# LoRa_DEMO.net
KiCad netlist of a schematic drawn in Altium Designer
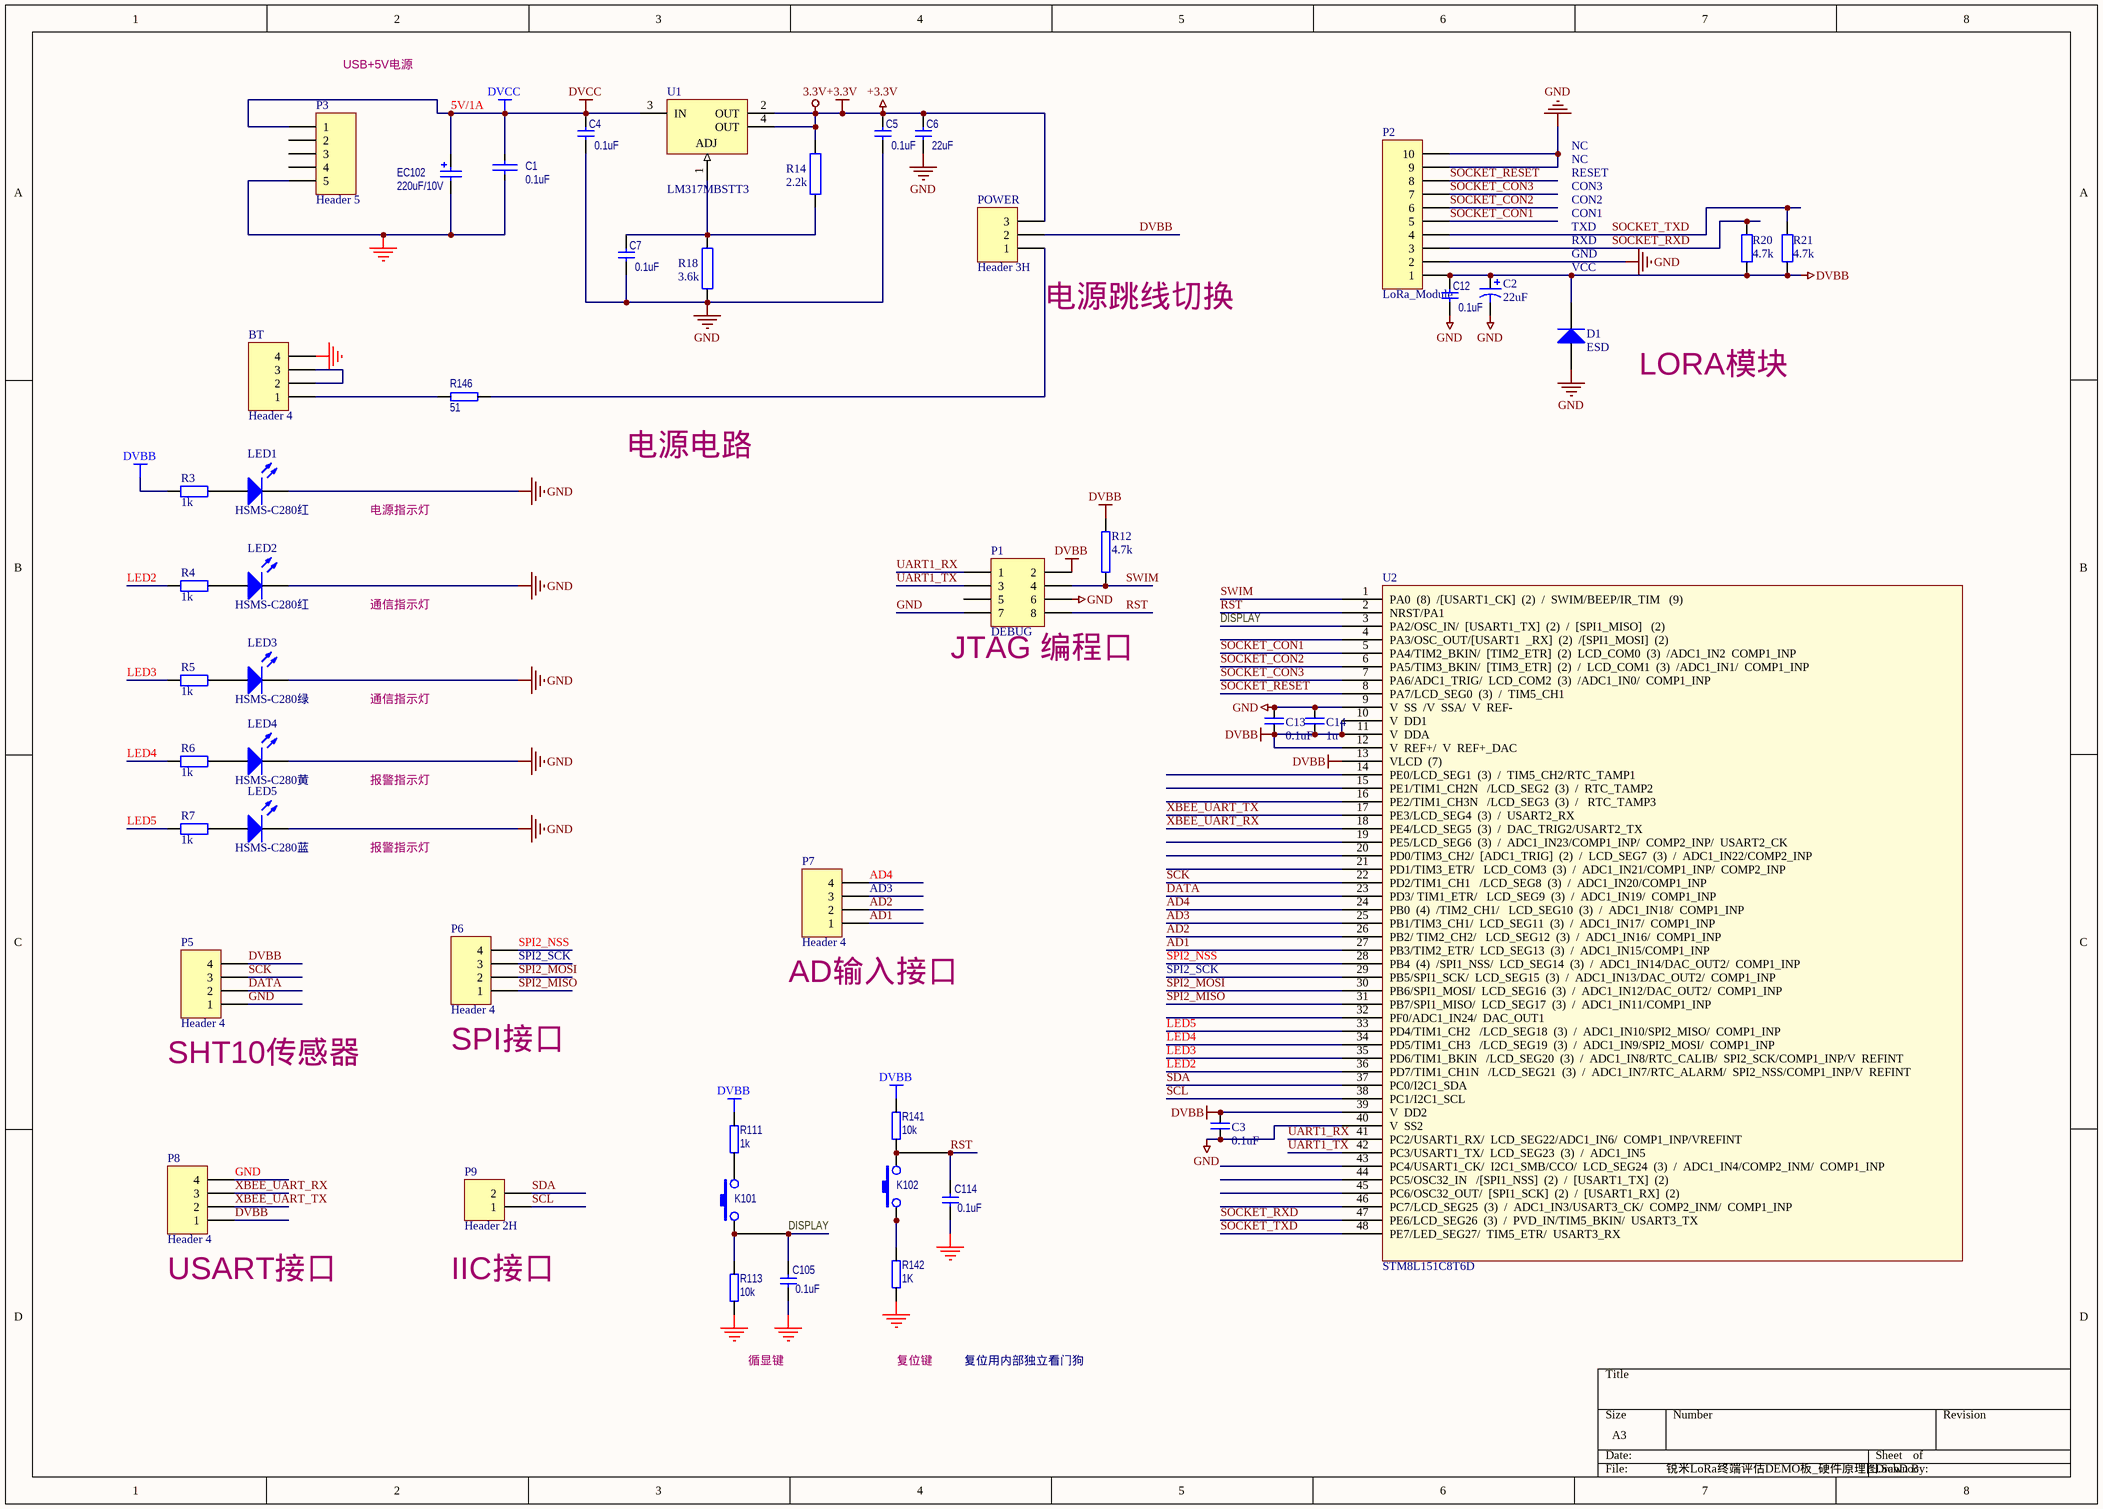
[diagram p0: 锐米LoRa终端评估DEMO板_硬件原理图.SchDoc]

(export (version "E")
  (design (tool "Eeschema 10.0.6"))
  (components
    (comp (ref "BT")
      (value "Header 4")
      (footprint "BT-1")
      (description "Header, 4-Pin")
      (fields (field (name "PUBLISHER") "Altium Limited"))
      (libsource (lib "Miscellaneous Connectors") (part "Header 4"))
    )
    (comp (ref "C1")
      (value "0.1uF")
      (footprint "0603C")
      (description "Capacitor")
      (libsource (lib "*") (part "CAP"))
    )
    (comp (ref "C2")
      (value "22uF")
      (footprint "3225[1210]")
      (description "Polarized Capacitor (Radial)")
      (fields (field (name "Comment") "Cap Pol1") (field (name "PUBLISHER") "Altium Limited"))
      (libsource (lib "Miscellaneous Devices") (part "Cap Pol1"))
    )
    (comp (ref "C3")
      (value "0.1uF")
      (footprint "0603C")
      (description "电容__贴片")
      (libsource (lib "*") (part "0603_50V_15pF±5% NPO"))
    )
    (comp (ref "C4") (value "0.1uF") (footprint "0603c") (libsource (lib "*") (part "ProE.tmp_22p_13")))
    (comp (ref "C5") (value "0.1uF") (footprint "0603C") (libsource (lib "*") (part "ProE.tmp_22p_13")))
    (comp (ref "C6") (value "22uF") (footprint "3225[1210]") (libsource (lib "*") (part "ProE.tmp_22p_13")))
    (comp (ref "C7") (value "0.1uF") (footprint "0603C") (libsource (lib "*") (part "ProE.tmp_22p_13")))
    (comp (ref "C12") (value "0.1uF") (footprint "0603C") (libsource (lib "*") (part "ProE.tmp_22p_13")))
    (comp (ref "C13")
      (value "0.1uF")
      (footprint "0603C")
      (description "电容__贴片")
      (libsource (lib "*") (part "0603_50V_15pF±5% NPO"))
    )
    (comp (ref "C14")
      (value "1u")
      (footprint "0603C")
      (description "电容__贴片")
      (libsource (lib "*") (part "0603_50V_15pF±5% NPO"))
    )
    (comp (ref "C105") (value "0.1uF") (footprint "0603C") (libsource (lib "*") (part "ProE.tmp_22p_13")))
    (comp (ref "C114") (value "0.1uF") (footprint "0603C") (libsource (lib "*") (part "ProE.tmp_22p_13")))
    (comp (ref "D1")
      (value "ESD")
      (footprint "SOD123/X.85")
      (description "Default Diode")
      (fields (field (name "PUBLISHER") "Altium Limited"))
      (libsource (lib "Miscellaneous Devices") (part "Diode"))
    )
    (comp (ref "EC102")
      (value "220uF/10V")
      (footprint "3225[1210]")
      (description "Polarized Capacitor (Radial)")
      (fields (field (name "PUBLISHER") "*"))
      (libsource (lib "*") (part "Cap Pol1"))
    )
    (comp (ref "K101") (value "~") (footprint "KEYSMT") (libsource (lib "*") (part "SW-PB")))
    (comp (ref "K102") (value "~") (footprint "KEYSMT") (libsource (lib "*") (part "SW-PB")))
    (comp (ref "LED1")
      (value "HSMS-C280红")
      (footprint "LED-SOP")
      (description "Miniature Chip LED, Red")
      (fields (field (name "PUBLISHER") "Altium Limited"))
      (libsource (lib "Agilent Optoelectronic LED") (part "HSMS-C280"))
    )
    (comp (ref "LED2")
      (value "HSMS-C280红")
      (footprint "LED-SOP")
      (description "Miniature Chip LED, Red")
      (fields (field (name "PUBLISHER") "Altium Limited"))
      (libsource (lib "Agilent Optoelectronic LED") (part "HSMS-C280"))
    )
    (comp (ref "LED3")
      (value "HSMS-C280绿")
      (footprint "LED-SOP")
      (description "Miniature Chip LED, Red")
      (fields (field (name "PUBLISHER") "Altium Limited"))
      (libsource (lib "Agilent Optoelectronic LED") (part "HSMS-C280"))
    )
    (comp (ref "LED4")
      (value "HSMS-C280黄")
      (footprint "LED-SOP")
      (description "Miniature Chip LED, Red")
      (fields (field (name "PUBLISHER") "Altium Limited"))
      (libsource (lib "Agilent Optoelectronic LED") (part "HSMS-C280"))
    )
    (comp (ref "LED5")
      (value "HSMS-C280蓝")
      (footprint "LED-SOP")
      (description "Miniature Chip LED, Red")
      (fields (field (name "PUBLISHER") "Altium Limited"))
      (libsource (lib "Agilent Optoelectronic LED") (part "HSMS-C280"))
    )
    (comp (ref "P1")
      (value "DEBUG")
      (footprint "HDR-2X7-F-1.27MM_8")
      (description "Header, 4-Pin, Dual row")
      (fields (field (name "PUBLISHER") "Altium Limited"))
      (libsource (lib "Miscellaneous Connectors") (part "Header 4X2"))
    )
    (comp (ref "P2")
      (value "LoRa_Module")
      (footprint "LIRDA")
      (description "Header, 10-Pin")
      (fields (field (name "PUBLISHER") "Altium Limited"))
      (libsource (lib "Miscellaneous Connectors") (part "Header 10"))
    )
    (comp (ref "P3")
      (value "Header 5")
      (footprint "USB-MINI")
      (description "Header, 5-Pin")
      (fields (field (name "PUBLISHER") "Altium Limited"))
      (libsource (lib "Miscellaneous Connectors") (part "Header 5"))
    )
    (comp (ref "P5")
      (value "Header 4")
      (footprint "SHT10")
      (description "Header, 4-Pin")
      (fields (field (name "PUBLISHER") "Altium Limited"))
      (libsource (lib "Miscellaneous Connectors") (part "Header 4"))
    )
    (comp (ref "P6")
      (value "Header 4")
      (footprint "HDR1X4")
      (description "Header, 4-Pin")
      (fields (field (name "PUBLISHER") "Altium Limited"))
      (libsource (lib "Miscellaneous Connectors") (part "Header 4"))
    )
    (comp (ref "P7")
      (value "Header 4")
      (footprint "HDR1X4")
      (description "Header, 4-Pin")
      (fields (field (name "PUBLISHER") "Altium Limited"))
      (libsource (lib "Miscellaneous Connectors") (part "Header 4"))
    )
    (comp (ref "P8")
      (value "Header 4")
      (footprint "HDR1X4")
      (description "Header, 4-Pin")
      (fields (field (name "PUBLISHER") "Altium Limited"))
      (libsource (lib "Miscellaneous Connectors") (part "Header 4"))
    )
    (comp (ref "P9")
      (value "Header 2H")
      (footprint "SIP2")
      (description "Header, 2-Pin, Right Angle")
      (fields (field (name "PUBLISHER") "Altium Limited"))
      (libsource (lib "Miscellaneous Connectors") (part "Header 2H"))
    )
    (comp (ref "POWER")
      (value "Header 3H")
      (footprint "SIP3")
      (description "Header, 3-Pin, Right Angle")
      (fields (field (name "PUBLISHER") "Altium Limited"))
      (libsource (lib "Miscellaneous Connectors") (part "Header 3H"))
    )
    (comp (ref "R3")
      (value "1k")
      (footprint "0603R")
      (description "Resistor SMD - IEC symbol version")
      (fields (field (name "Comment") "Resistor"))
      (libsource (lib "SX1276_e268v01a") (part "Resistor"))
    )
    (comp (ref "R4")
      (value "1k")
      (footprint "0603R")
      (description "Resistor SMD - IEC symbol version")
      (fields (field (name "Comment") "Resistor"))
      (libsource (lib "SX1276_e268v01a") (part "Resistor"))
    )
    (comp (ref "R5")
      (value "1k")
      (footprint "0603R")
      (description "Resistor SMD - IEC symbol version")
      (fields (field (name "Comment") "Resistor"))
      (libsource (lib "SX1276_e268v01a") (part "Resistor"))
    )
    (comp (ref "R6")
      (value "1k")
      (footprint "0603R")
      (description "Resistor SMD - IEC symbol version")
      (fields (field (name "Comment") "Resistor"))
      (libsource (lib "SX1276_e268v01a") (part "Resistor"))
    )
    (comp (ref "R7")
      (value "1k")
      (footprint "0603R")
      (description "Resistor SMD - IEC symbol version")
      (fields (field (name "Comment") "Resistor"))
      (libsource (lib "SX1276_e268v01a") (part "Resistor"))
    )
    (comp (ref "R12")
      (value "4.7k")
      (footprint "0603R")
      (description "¹qªý")
      (libsource (lib "*") (part "RES2"))
    )
    (comp (ref "R14")
      (value "2.2k")
      (footprint "0603R")
      (description "电阻_贴片")
      (libsource (lib "*") (part "0603_20kΩ±1%100ppm/℃"))
    )
    (comp (ref "R18")
      (value "3.6k")
      (footprint "0603R")
      (description "电阻_贴片")
      (libsource (lib "*") (part "0603_20kΩ±1%100ppm/℃"))
    )
    (comp (ref "R20")
      (value "4.7k")
      (footprint "0603R")
      (description "Resistor SMD - IEC symbol version")
      (fields (field (name "Comment") "Resistor"))
      (libsource (lib "") (part "Resistor_1"))
    )
    (comp (ref "R21")
      (value "4.7k")
      (footprint "0603R")
      (description "Resistor SMD - IEC symbol version")
      (fields (field (name "Comment") "Resistor"))
      (libsource (lib "") (part "Resistor_1"))
    )
    (comp (ref "R111") (value "1k") (footprint "0603R") (libsource (lib "*") (part "ProE.tmp_10k_66")))
    (comp (ref "R113") (value "10k") (footprint "0603R") (libsource (lib "*") (part "ProE.tmp_10k_66")))
    (comp (ref "R141") (value "10k") (footprint "0603R") (libsource (lib "*") (part "ProE.tmp_10k_66")))
    (comp (ref "R142") (value "1K") (footprint "0603R") (libsource (lib "*") (part "ProE.tmp_10k_66")))
    (comp (ref "R146") (value "51") (footprint "0603R") (libsource (lib "*") (part "ProE.tmp_10k_66")))
    (comp (ref "U1")
      (value "LM317MBSTT3")
      (footprint "318E-04")
      (description "Three-Terminal Adjustable Output Positive Voltage Regulator")
      (fields (field (name "PUBLISHER") "Altium Limited"))
      (libsource (lib "ON Semi Power Mgt Voltage Regulator") (part "LM317MBSTT3"))
    )
    (comp (ref "U2")
      (value "STM8L151C8T6D")
      (footprint "LQFP48_L")
      (libsource (lib "Schlib1") (part "Component_1"))
    )
  )
  (nets
    (net (code "1") (name "+3.3V") (class "Default")
      (node (ref "C5") (pin "1") (pintype "passive"))
      (node (ref "C6") (pin "1") (pintype "passive"))
      (node (ref "POWER") (pin "3") (pinfunction "3_3") (pintype "passive"))
      (node (ref "R14") (pin "1") (pintype "passive"))
      (node (ref "U1") (pin "2") (pinfunction "OUT_2") (pintype "power_in"))
      (node (ref "U1") (pin "4") (pinfunction "OUT_4") (pintype "power_in"))
    )
    (net (code "2") (name "/AD1") (class "Default")
      (node (ref "P7") (pin "1") (pinfunction "1_1") (pintype "passive"))
      (node (ref "U2") (pin "27") (pinfunction "PB3/TIM2_ETR/__LCD_SEG13__(3)__/__ADC1_IN15/COMP1_INP_27") (pintype "passive"))
    )
    (net (code "3") (name "/AD2") (class "Default")
      (node (ref "P7") (pin "2") (pinfunction "2_2") (pintype "passive"))
      (node (ref "U2") (pin "26") (pinfunction "PB2/_TIM2_CH2/___LCD_SEG12__(3)__/__ADC1_IN16/__COMP1_INP_26") (pintype "passive"))
    )
    (net (code "4") (name "/AD3") (class "Default")
      (node (ref "P7") (pin "3") (pinfunction "3_3") (pintype "passive"))
      (node (ref "U2") (pin "25") (pinfunction "PB1/TIM3_CH1/__LCD_SEG11__(3)__/__ADC1_IN17/__COMP1_INP_25") (pintype "passive"))
    )
    (net (code "5") (name "/AD4") (class "Default")
      (node (ref "P7") (pin "4") (pinfunction "4_4") (pintype "passive"))
      (node (ref "U2") (pin "24") (pinfunction "PB0__(4)__/TIM2_CH1/___LCD_SEG10__(3)__/__ADC1_IN18/__COMP1_INP_24") (pintype "passive"))
    )
    (net (code "6") (name "/DATA") (class "Default")
      (node (ref "P5") (pin "2") (pinfunction "2_2") (pintype "passive"))
      (node (ref "U2") (pin "23") (pinfunction "PD3/_TIM1_ETR/___LCD_SEG9__(3)__/__ADC1_IN19/__COMP1_INP_23") (pintype "passive"))
    )
    (net (code "7") (name "/DISPLAY") (class "Default")
      (node (ref "C105") (pin "1") (pintype "passive"))
      (node (ref "K101") (pin "2") (pinfunction "2_2") (pintype "passive"))
      (node (ref "R113") (pin "1") (pintype "passive"))
      (node (ref "U2") (pin "3") (pinfunction "PA2/OSC_IN/__[USART1_TX]__(2)__/__[SPI1_MISO]___(2)_3") (pintype "passive"))
    )
    (net (code "8") (name "/LED2") (class "Default")
      (node (ref "R4") (pin "1") (pinfunction "1_1") (pintype "passive"))
      (node (ref "U2") (pin "36") (pinfunction "PD7/TIM1_CH1N___/LCD_SEG21__(3)__/__ADC1_IN7/RTC_ALARM/__SPI2_NSS/COMP1_INP/V__REFINT_36") (pintype "passive"))
    )
    (net (code "9") (name "/LED3") (class "Default")
      (node (ref "R5") (pin "1") (pinfunction "1_1") (pintype "passive"))
      (node (ref "U2") (pin "35") (pinfunction "PD6/TIM1_BKIN___/LCD_SEG20__(3)__/__ADC1_IN8/RTC_CALIB/__SPI2_SCK/COMP1_INP/V__REFINT_35") (pintype "passive"))
    )
    (net (code "10") (name "/LED4") (class "Default")
      (node (ref "R6") (pin "1") (pinfunction "1_1") (pintype "passive"))
      (node (ref "U2") (pin "34") (pinfunction "PD5/TIM1_CH3___/LCD_SEG19__(3)__/__ADC1_IN9/SPI2_MOSI/__COMP1_INP_34") (pintype "passive"))
    )
    (net (code "11") (name "/LED5") (class "Default")
      (node (ref "R7") (pin "1") (pinfunction "1_1") (pintype "passive"))
      (node (ref "U2") (pin "33") (pinfunction "PD4/TIM1_CH2___/LCD_SEG18__(3)__/__ADC1_IN10/SPI2_MISO/__COMP1_INP_33") (pintype "passive"))
    )
    (net (code "12") (name "/RST") (class "Default")
      (node (ref "C114") (pin "1") (pintype "passive"))
      (node (ref "K102") (pin "1") (pinfunction "1_1") (pintype "passive"))
      (node (ref "P1") (pin "8") (pinfunction "8_8") (pintype "passive"))
      (node (ref "R141") (pin "2") (pintype "passive"))
      (node (ref "U2") (pin "2") (pinfunction "NRST/PA1_2") (pintype "passive"))
    )
    (net (code "13") (name "/SCK") (class "Default")
      (node (ref "P5") (pin "3") (pinfunction "3_3") (pintype "passive"))
      (node (ref "U2") (pin "22") (pinfunction "PD2/TIM1_CH1___/LCD_SEG8__(3)__/__ADC1_IN20/COMP1_INP_22") (pintype "passive"))
    )
    (net (code "14") (name "/SCL") (class "Default")
      (node (ref "P9") (pin "1") (pinfunction "1_1") (pintype "passive"))
      (node (ref "U2") (pin "38") (pinfunction "PC1/I2C1_SCL_38") (pintype "passive"))
    )
    (net (code "15") (name "/SDA") (class "Default")
      (node (ref "P9") (pin "2") (pinfunction "2_2") (pintype "passive"))
      (node (ref "U2") (pin "37") (pinfunction "PC0/I2C1_SDA_37") (pintype "passive"))
    )
    (net (code "16") (name "/SOCKET_CON1") (class "Default")
      (node (ref "P2") (pin "5") (pinfunction "5_5") (pintype "passive"))
      (node (ref "U2") (pin "5") (pinfunction "PA4/TIM2_BKIN/__[TIM2_ETR]__(2)__LCD_COM0__(3)__/ADC1_IN2__COMP1_INP_5") (pintype "passive"))
    )
    (net (code "17") (name "/SOCKET_CON2") (class "Default")
      (node (ref "P2") (pin "6") (pinfunction "6_6") (pintype "passive"))
      (node (ref "U2") (pin "6") (pinfunction "PA5/TIM3_BKIN/__[TIM3_ETR]__(2)__/__LCD_COM1__(3)__/ADC1_IN1/__COMP1_INP_6") (pintype "passive"))
    )
    (net (code "18") (name "/SOCKET_CON3") (class "Default")
      (node (ref "P2") (pin "7") (pinfunction "7_7") (pintype "passive"))
      (node (ref "U2") (pin "7") (pinfunction "PA6/ADC1_TRIG/__LCD_COM2__(3)__/ADC1_IN0/__COMP1_INP_7") (pintype "passive"))
    )
    (net (code "19") (name "/SOCKET_RESET") (class "Default")
      (node (ref "P2") (pin "8") (pinfunction "8_8") (pintype "passive"))
      (node (ref "U2") (pin "8") (pinfunction "PA7/LCD_SEG0__(3)__/__TIM5_CH1_8") (pintype "passive"))
    )
    (net (code "20") (name "/SOCKET_RXD") (class "Default")
      (node (ref "P2") (pin "3") (pinfunction "3_3") (pintype "passive"))
      (node (ref "R20") (pin "2") (pinfunction "2_2") (pintype "passive"))
      (node (ref "U2") (pin "47") (pinfunction "PE6/LCD_SEG26__(3)__/__PVD_IN/TIM5_BKIN/__USART3_TX_47") (pintype "passive"))
    )
    (net (code "21") (name "/SOCKET_TXD") (class "Default")
      (node (ref "P2") (pin "4") (pinfunction "4_4") (pintype "passive"))
      (node (ref "R21") (pin "2") (pinfunction "2_2") (pintype "passive"))
      (node (ref "U2") (pin "48") (pinfunction "PE7/LED_SEG27/__TIM5_ETR/__USART3_RX_48") (pintype "passive"))
    )
    (net (code "22") (name "/SPI2_MISO") (class "Default")
      (node (ref "P6") (pin "1") (pinfunction "1_1") (pintype "passive"))
      (node (ref "U2") (pin "31") (pinfunction "PB7/SPI1_MISO/__LCD_SEG17__(3)__/__ADC1_IN11/COMP1_INP_31") (pintype "passive"))
    )
    (net (code "23") (name "/SPI2_MOSI") (class "Default")
      (node (ref "P6") (pin "2") (pinfunction "2_2") (pintype "passive"))
      (node (ref "U2") (pin "30") (pinfunction "PB6/SPI1_MOSI/__LCD_SEG16__(3)__/__ADC1_IN12/DAC_OUT2/__COMP1_INP_30") (pintype "passive"))
    )
    (net (code "24") (name "/SPI2_NSS") (class "Default")
      (node (ref "P6") (pin "4") (pinfunction "4_4") (pintype "passive"))
      (node (ref "U2") (pin "28") (pinfunction "PB4__(4)__/SPI1_NSS/__LCD_SEG14__(3)__/__ADC1_IN14/DAC_OUT2/__COMP1_INP_28") (pintype "passive"))
    )
    (net (code "25") (name "/SPI2_SCK") (class "Default")
      (node (ref "P6") (pin "3") (pinfunction "3_3") (pintype "passive"))
      (node (ref "U2") (pin "29") (pinfunction "PB5/SPI1_SCK/__LCD_SEG15__(3)__/__ADC1_IN13/DAC_OUT2/__COMP1_INP_29") (pintype "passive"))
    )
    (net (code "26") (name "/SWIM") (class "Default")
      (node (ref "P1") (pin "4") (pinfunction "4_4") (pintype "passive"))
      (node (ref "R12") (pin "1") (pinfunction "1_1") (pintype "passive"))
      (node (ref "U2") (pin "1") (pinfunction "PA0__(8)__/[USART1_CK]__(2)__/__SWIM/BEEP/IR_TIM___(9)_1") (pintype "passive"))
    )
    (net (code "27") (name "/UART1_RX") (class "Default")
      (node (ref "P1") (pin "1") (pinfunction "1_1") (pintype "passive"))
      (node (ref "U2") (pin "41") (pinfunction "PC2/USART1_RX/__LCD_SEG22/ADC1_IN6/__COMP1_INP/VREFINT_41") (pintype "passive"))
    )
    (net (code "28") (name "/UART1_TX") (class "Default")
      (node (ref "P1") (pin "3") (pinfunction "3_3") (pintype "passive"))
      (node (ref "U2") (pin "42") (pinfunction "PC3/USART1_TX/__LCD_SEG23__(3)__/__ADC1_IN5_42") (pintype "passive"))
    )
    (net (code "29") (name "/XBEE_UART_RX") (class "Default")
      (node (ref "P8") (pin "3") (pinfunction "3_3") (pintype "passive"))
      (node (ref "U2") (pin "18") (pinfunction "PE4/LCD_SEG5__(3)__/__DAC_TRIG2/USART2_TX_18") (pintype "passive"))
    )
    (net (code "30") (name "/XBEE_UART_TX") (class "Default")
      (node (ref "P8") (pin "2") (pinfunction "2_2") (pintype "passive"))
      (node (ref "U2") (pin "17") (pinfunction "PE3/LCD_SEG4__(3)__/__USART2_RX_17") (pintype "passive"))
    )
    (net (code "31") (name "DVBB") (class "Default")
      (node (ref "C12") (pin "1") (pintype "passive"))
      (node (ref "C13") (pin "1") (pintype "passive"))
      (node (ref "C14") (pin "1") (pintype "passive"))
      (node (ref "C2") (pin "1") (pinfunction "1_1") (pintype "passive"))
      (node (ref "C3") (pin "2") (pintype "passive"))
      (node (ref "D1") (pin "2") (pinfunction "K_2") (pintype "passive"))
      (node (ref "P1") (pin "2") (pinfunction "2_2") (pintype "passive"))
      (node (ref "P2") (pin "1") (pinfunction "1_1") (pintype "passive"))
      (node (ref "P5") (pin "4") (pinfunction "4_4") (pintype "passive"))
      (node (ref "P8") (pin "1") (pinfunction "1_1") (pintype "passive"))
      (node (ref "POWER") (pin "2") (pinfunction "2_2") (pintype "passive"))
      (node (ref "R111") (pin "1") (pintype "passive"))
      (node (ref "R12") (pin "2") (pinfunction "2_2") (pintype "passive"))
      (node (ref "R141") (pin "1") (pintype "passive"))
      (node (ref "R20") (pin "1") (pinfunction "1_1") (pintype "passive"))
      (node (ref "R21") (pin "1") (pinfunction "1_1") (pintype "passive"))
      (node (ref "R3") (pin "1") (pinfunction "1_1") (pintype "passive"))
      (node (ref "U2") (pin "10") (pinfunction "V__DD1_10") (pintype "passive"))
      (node (ref "U2") (pin "11") (pinfunction "V__DDA_11") (pintype "passive"))
      (node (ref "U2") (pin "12") (pinfunction "V__REF+/__V__REF+_DAC_12") (pintype "passive"))
      (node (ref "U2") (pin "13") (pinfunction "VLCD__(7)_13") (pintype "passive"))
      (node (ref "U2") (pin "39") (pinfunction "V__DD2_39") (pintype "passive"))
    )
    (net (code "32") (name "DVCC") (class "Default")
      (node (ref "C1") (pin "1") (pinfunction "1_1") (pintype "passive"))
      (node (ref "C4") (pin "1") (pintype "passive"))
      (node (ref "EC102") (pin "1") (pinfunction "1_1") (pintype "passive"))
      (node (ref "P3") (pin "1") (pinfunction "1_1") (pintype "passive"))
      (node (ref "U1") (pin "3") (pinfunction "IN_3") (pintype "power_in"))
    )
    (net (code "33") (name "GND") (class "Default")
      (node (ref "BT") (pin "4") (pinfunction "4_4") (pintype "passive"))
      (node (ref "C1") (pin "2") (pinfunction "2_2") (pintype "passive"))
      (node (ref "C105") (pin "2") (pintype "passive"))
      (node (ref "C114") (pin "2") (pintype "passive"))
      (node (ref "C12") (pin "2") (pintype "passive"))
      (node (ref "C13") (pin "2") (pintype "passive"))
      (node (ref "C14") (pin "2") (pintype "passive"))
      (node (ref "C2") (pin "2") (pinfunction "2_2") (pintype "passive"))
      (node (ref "C3") (pin "1") (pintype "passive"))
      (node (ref "C4") (pin "2") (pintype "passive"))
      (node (ref "C5") (pin "2") (pintype "passive"))
      (node (ref "C6") (pin "2") (pintype "passive"))
      (node (ref "C7") (pin "2") (pintype "passive"))
      (node (ref "D1") (pin "1") (pinfunction "A_1") (pintype "passive"))
      (node (ref "EC102") (pin "2") (pinfunction "2_2") (pintype "passive"))
      (node (ref "LED1") (pin "2") (pinfunction "K_2") (pintype "passive"))
      (node (ref "LED2") (pin "2") (pinfunction "K_2") (pintype "passive"))
      (node (ref "LED3") (pin "2") (pinfunction "K_2") (pintype "passive"))
      (node (ref "LED4") (pin "2") (pinfunction "K_2") (pintype "passive"))
      (node (ref "LED5") (pin "2") (pinfunction "K_2") (pintype "passive"))
      (node (ref "P1") (pin "6") (pinfunction "6_6") (pintype "passive"))
      (node (ref "P1") (pin "7") (pinfunction "7_7") (pintype "passive"))
      (node (ref "P2") (pin "10") (pinfunction "10_10") (pintype "passive"))
      (node (ref "P2") (pin "2") (pinfunction "2_2") (pintype "passive"))
      (node (ref "P2") (pin "9") (pinfunction "9_9") (pintype "passive"))
      (node (ref "P3") (pin "5") (pinfunction "5_5") (pintype "passive"))
      (node (ref "P5") (pin "1") (pinfunction "1_1") (pintype "passive"))
      (node (ref "P8") (pin "4") (pinfunction "4_4") (pintype "passive"))
      (node (ref "R113") (pin "2") (pintype "passive"))
      (node (ref "R142") (pin "1") (pintype "passive"))
      (node (ref "R18") (pin "2") (pintype "passive"))
      (node (ref "U2") (pin "40") (pinfunction "V__SS2_40") (pintype "passive"))
      (node (ref "U2") (pin "9") (pinfunction "V__SS__/V__SSA/__V__REF-_9") (pintype "passive"))
    )
    (net (code "34") (name "Net-(BT-Pad1)") (class "Default")
      (node (ref "BT") (pin "1") (pinfunction "1_1") (pintype "passive"))
      (node (ref "R146") (pin "2") (pintype "passive"))
    )
    (net (code "35") (name "Net-(BT-Pad2)") (class "Default")
      (node (ref "BT") (pin "2") (pinfunction "2_2") (pintype "passive"))
      (node (ref "BT") (pin "3") (pinfunction "3_3") (pintype "passive"))
    )
    (net (code "36") (name "Net-(K101-Pad1)") (class "Default")
      (node (ref "K101") (pin "1") (pinfunction "1_1") (pintype "passive"))
      (node (ref "R111") (pin "2") (pintype "passive"))
    )
    (net (code "37") (name "Net-(K102-Pad2)") (class "Default")
      (node (ref "K102") (pin "2") (pinfunction "2_2") (pintype "passive"))
      (node (ref "R142") (pin "2") (pintype "passive"))
    )
    (net (code "38") (name "Net-(LED1-A)") (class "Default")
      (node (ref "LED1") (pin "1") (pinfunction "A_1") (pintype "passive"))
      (node (ref "R3") (pin "2") (pinfunction "2_2") (pintype "passive"))
    )
    (net (code "39") (name "Net-(LED2-A)") (class "Default")
      (node (ref "LED2") (pin "1") (pinfunction "A_1") (pintype "passive"))
      (node (ref "R4") (pin "2") (pinfunction "2_2") (pintype "passive"))
    )
    (net (code "40") (name "Net-(LED3-A)") (class "Default")
      (node (ref "LED3") (pin "1") (pinfunction "A_1") (pintype "passive"))
      (node (ref "R5") (pin "2") (pinfunction "2_2") (pintype "passive"))
    )
    (net (code "41") (name "Net-(LED4-A)") (class "Default")
      (node (ref "LED4") (pin "1") (pinfunction "A_1") (pintype "passive"))
      (node (ref "R6") (pin "2") (pinfunction "2_2") (pintype "passive"))
    )
    (net (code "42") (name "Net-(LED5-A)") (class "Default")
      (node (ref "LED5") (pin "1") (pinfunction "A_1") (pintype "passive"))
      (node (ref "R7") (pin "2") (pinfunction "2_2") (pintype "passive"))
    )
    (net (code "43") (name "Net-(POWER-Pad1)") (class "Default")
      (node (ref "POWER") (pin "1") (pinfunction "1_1") (pintype "passive"))
      (node (ref "R146") (pin "1") (pintype "passive"))
    )
    (net (code "44") (name "Net-(U1-ADJ)") (class "Default")
      (node (ref "C7") (pin "1") (pintype "passive"))
      (node (ref "R14") (pin "2") (pintype "passive"))
      (node (ref "R18") (pin "1") (pintype "passive"))
      (node (ref "U1") (pin "1") (pinfunction "ADJ_1") (pintype "input"))
    )
    (net (code "45") (name "unconnected-(P1-Pad5)") (class "Default")
      (node (ref "P1") (pin "5") (pinfunction "5_5") (pintype "passive"))
    )
    (net (code "46") (name "unconnected-(P3-Pad2)") (class "Default")
      (node (ref "P3") (pin "2") (pinfunction "2_2") (pintype "passive"))
    )
    (net (code "47") (name "unconnected-(P3-Pad3)") (class "Default")
      (node (ref "P3") (pin "3") (pinfunction "3_3") (pintype "passive"))
    )
    (net (code "48") (name "unconnected-(P3-Pad4)") (class "Default")
      (node (ref "P3") (pin "4") (pinfunction "4_4") (pintype "passive"))
    )
    (net (code "49") (name "unconnected-(U2-PA3{slash}OSC_OUT{slash}[USART1___RX]__(2)__{slash}[SPI1_MOSI]__(2)-Pad4)") (class "Default")
      (node (ref "U2") (pin "4") (pinfunction "PA3/OSC_OUT/[USART1___RX]__(2)__/[SPI1_MOSI]__(2)_4") (pintype "passive"))
    )
    (net (code "50") (name "unconnected-(U2-PC4{slash}USART1_CK{slash}__I2C1_SMB{slash}CCO{slash}__LCD_SEG24__(3)__{slash}__ADC1_IN4{slash}COMP2_INM{slash}__COMP1_INP-Pad43)") (class "Default")
      (node (ref "U2") (pin "43") (pinfunction "PC4/USART1_CK/__I2C1_SMB/CCO/__LCD_SEG24__(3)__/__ADC1_IN4/COMP2_INM/__COMP1_INP_43") (pintype "passive"))
    )
    (net (code "51") (name "unconnected-(U2-PC5{slash}OSC32_IN___{slash}[SPI1_NSS]__(2)__{slash}__[USART1_TX]__(2)-Pad44)") (class "Default")
      (node (ref "U2") (pin "44") (pinfunction "PC5/OSC32_IN___/[SPI1_NSS]__(2)__/__[USART1_TX]__(2)_44") (pintype "passive"))
    )
    (net (code "52") (name "unconnected-(U2-PC6{slash}OSC32_OUT{slash}__[SPI1_SCK]__(2)__{slash}__[USART1_RX]__(2)-Pad45)") (class "Default")
      (node (ref "U2") (pin "45") (pinfunction "PC6/OSC32_OUT/__[SPI1_SCK]__(2)__/__[USART1_RX]__(2)_45") (pintype "passive"))
    )
    (net (code "53") (name "unconnected-(U2-PC7{slash}LCD_SEG25__(3)__{slash}__ADC1_IN3{slash}USART3_CK{slash}__COMP2_INM{slash}__COMP1_INP-Pad46)") (class "Default")
      (node (ref "U2") (pin "46") (pinfunction "PC7/LCD_SEG25__(3)__/__ADC1_IN3/USART3_CK/__COMP2_INM/__COMP1_INP_46") (pintype "passive"))
    )
    (net (code "54") (name "unconnected-(U2-PD0{slash}TIM3_CH2{slash}__[ADC1_TRIG]__(2)__{slash}__LCD_SEG7__(3)__{slash}__ADC1_IN22{slash}COMP2_INP-Pad20)") (class "Default")
      (node (ref "U2") (pin "20") (pinfunction "PD0/TIM3_CH2/__[ADC1_TRIG]__(2)__/__LCD_SEG7__(3)__/__ADC1_IN22/COMP2_INP_20") (pintype "passive"))
    )
    (net (code "55") (name "unconnected-(U2-PD1{slash}TIM3_ETR{slash}___LCD_COM3__(3)__{slash}__ADC1_IN21{slash}COMP1_INP{slash}__COMP2_INP-Pad21)") (class "Default")
      (node (ref "U2") (pin "21") (pinfunction "PD1/TIM3_ETR/___LCD_COM3__(3)__/__ADC1_IN21/COMP1_INP/__COMP2_INP_21") (pintype "passive"))
    )
    (net (code "56") (name "unconnected-(U2-PE0{slash}LCD_SEG1__(3)__{slash}__TIM5_CH2{slash}RTC_TAMP1-Pad14)") (class "Default")
      (node (ref "U2") (pin "14") (pinfunction "PE0/LCD_SEG1__(3)__/__TIM5_CH2/RTC_TAMP1_14") (pintype "passive"))
    )
    (net (code "57") (name "unconnected-(U2-PE1{slash}TIM1_CH2N___{slash}LCD_SEG2__(3)__{slash}__RTC_TAMP2-Pad15)") (class "Default")
      (node (ref "U2") (pin "15") (pinfunction "PE1/TIM1_CH2N___/LCD_SEG2__(3)__/__RTC_TAMP2_15") (pintype "passive"))
    )
    (net (code "58") (name "unconnected-(U2-PE2{slash}TIM1_CH3N___{slash}LCD_SEG3__(3)__{slash}___RTC_TAMP3-Pad16)") (class "Default")
      (node (ref "U2") (pin "16") (pinfunction "PE2/TIM1_CH3N___/LCD_SEG3__(3)__/___RTC_TAMP3_16") (pintype "passive"))
    )
    (net (code "59") (name "unconnected-(U2-PE5{slash}LCD_SEG6__(3)__{slash}__ADC1_IN23{slash}COMP1_INP{slash}__COMP2_INP{slash}__USART2_CK-Pad19)") (class "Default")
      (node (ref "U2") (pin "19") (pinfunction "PE5/LCD_SEG6__(3)__/__ADC1_IN23/COMP1_INP/__COMP2_INP/__USART2_CK_19") (pintype "passive"))
    )
    (net (code "60") (name "unconnected-(U2-PF0{slash}ADC1_IN24{slash}__DAC_OUT1-Pad32)") (class "Default")
      (node (ref "U2") (pin "32") (pinfunction "PF0/ADC1_IN24/__DAC_OUT1_32") (pintype "passive"))
    )
  )
)
